# tritiled_v30.net
KiCad netlist of a schematic drawn in EAGLE
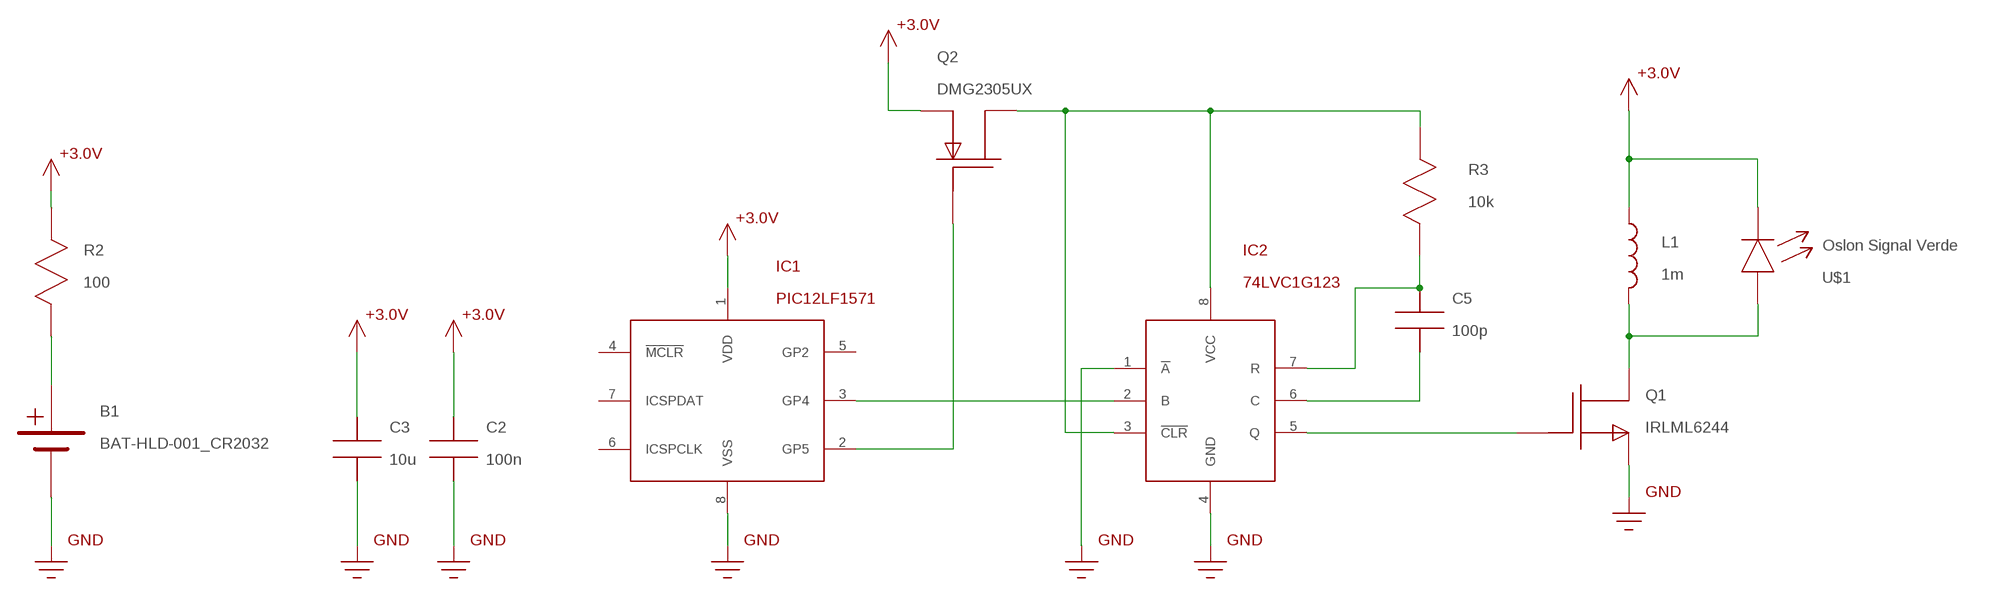
[diagram p0: schematic, sheet 1]

(export (version "E")
  (design (tool "Eeschema 10.0.6"))
  (components
    (comp (ref "B1")
      (value "BAT-HLD-001_CR2032")
      (footprint "eagle-import:CR2032_BAT-HLD_001")
      (libsource (lib "eagle-import") (part "BAT-HLD-001_CR2032"))
    )
    (comp (ref "C2")
      (value "100n")
      (footprint "eagle-import:0805")
      (libsource (lib "eagle-import") (part "C0805"))
    )
    (comp (ref "C3")
      (value "10u")
      (footprint "eagle-import:1206")
      (libsource (lib "eagle-import") (part "C1206"))
    )
    (comp (ref "C5")
      (value "100p")
      (footprint "eagle-import:C0603")
      (libsource (lib "eagle-import") (part "C0603"))
    )
    (comp (ref "IC1")
      (value "PIC12LF1571")
      (footprint "eagle-import:SOIC8")
      (libsource (lib "eagle-import") (part "PIC12LF1571"))
    )
    (comp (ref "IC2")
      (value "74LVC1G123")
      (footprint "eagle-import:SM8")
      (libsource (lib "eagle-import") (part "74LVC1G123"))
    )
    (comp (ref "L1")
      (value "1m")
      (footprint "eagle-import:SRR6028_INDUCTOR")
      (libsource (lib "eagle-import") (part "SRR6028_INDUCTOR"))
    )
    (comp (ref "Q1")
      (value "IRLML6244")
      (footprint "eagle-import:SOT-23")
      (libsource (lib "eagle-import") (part "ZXMN3B01FSOT23"))
    )
    (comp (ref "Q2")
      (value "DMG2305UX")
      (footprint "eagle-import:SOT-23")
      (libsource (lib "eagle-import") (part "DMG2305UXSOT23"))
    )
    (comp (ref "R2")
      (value "100")
      (footprint "eagle-import:R1206")
      (libsource (lib "eagle-import") (part "R1206"))
    )
    (comp (ref "R3")
      (value "10k")
      (footprint "eagle-import:R0603")
      (libsource (lib "eagle-import") (part "R0603"))
    )
    (comp (ref "U$1")
      (value "Oslon Signal Verde")
      (footprint "eagle-import:OSLON_3030_LED")
      (libsource (lib "eagle-import") (part "OSLON_SIGNAL"))
    )
  )
  (nets
    (net (code "1") (name "+3.0V") (class "Default")
      (node (ref "C2") (pin "P$1") (pinfunction "P$1_P$1") (pintype "bidirectional"))
      (node (ref "C3") (pin "P$1") (pinfunction "P$1_P$1") (pintype "bidirectional"))
      (node (ref "IC1") (pin "1") (pinfunction "VDD_1") (pintype "bidirectional"))
      (node (ref "L1") (pin "P$1") (pinfunction "1_P$1") (pintype "passive"))
      (node (ref "Q2") (pin "2") (pinfunction "S_2") (pintype "bidirectional"))
      (node (ref "R2") (pin "P$1") (pinfunction "P$1_P$1") (pintype "bidirectional"))
      (node (ref "U$1") (pin "C") (pinfunction "C_C") (pintype "bidirectional"))
    )
    (net (code "2") (name "GND") (class "Default")
      (node (ref "B1") (pin "GND") (pinfunction "0V_GND") (pintype "power_in"))
      (node (ref "C2") (pin "P$2") (pinfunction "P$2_P$2") (pintype "bidirectional"))
      (node (ref "C3") (pin "P$2") (pinfunction "P$2_P$2") (pintype "bidirectional"))
      (node (ref "IC1") (pin "8") (pinfunction "VSS_8") (pintype "bidirectional"))
      (node (ref "IC2") (pin "1") (pinfunction "~{A}_1") (pintype "bidirectional"))
      (node (ref "IC2") (pin "4") (pinfunction "GND_4") (pintype "bidirectional"))
      (node (ref "Q1") (pin "2") (pinfunction "S_2") (pintype "bidirectional"))
    )
    (net (code "3") (name "Net-(B1-+V-Pad+V1)") (class "Default")
      (node (ref "B1") (pin "+V1") (pinfunction "+V_+V1") (pintype "power_in"))
      (node (ref "B1") (pin "+V2") (pinfunction "+V_+V2") (pintype "power_in"))
      (node (ref "R2") (pin "P$2") (pinfunction "P$2_P$2") (pintype "bidirectional"))
    )
    (net (code "4") (name "Net-(IC1-GP4)") (class "Default")
      (node (ref "IC1") (pin "3") (pinfunction "GP4_3") (pintype "bidirectional"))
      (node (ref "IC2") (pin "2") (pinfunction "B_2") (pintype "bidirectional"))
    )
    (net (code "5") (name "Net-(IC1-GP5)") (class "Default")
      (node (ref "IC1") (pin "2") (pinfunction "GP5_2") (pintype "bidirectional"))
      (node (ref "Q2") (pin "1") (pinfunction "G_1") (pintype "bidirectional"))
    )
    (net (code "6") (name "Net-(IC2-C)") (class "Default")
      (node (ref "C5") (pin "P$2") (pinfunction "P$2_P$2") (pintype "bidirectional"))
      (node (ref "IC2") (pin "6") (pinfunction "C_6") (pintype "bidirectional"))
    )
    (net (code "7") (name "Net-(IC2-Q)") (class "Default")
      (node (ref "IC2") (pin "5") (pinfunction "Q_5") (pintype "bidirectional"))
      (node (ref "Q1") (pin "1") (pinfunction "G_1") (pintype "bidirectional"))
    )
    (net (code "8") (name "Net-(IC2-R)") (class "Default")
      (node (ref "C5") (pin "P$1") (pinfunction "P$1_P$1") (pintype "bidirectional"))
      (node (ref "IC2") (pin "7") (pinfunction "R_7") (pintype "bidirectional"))
      (node (ref "R3") (pin "P$1") (pinfunction "P$1_P$1") (pintype "bidirectional"))
    )
    (net (code "9") (name "Net-(IC2-VCC)") (class "Default")
      (node (ref "IC2") (pin "3") (pinfunction "~{CLR}_3") (pintype "bidirectional"))
      (node (ref "IC2") (pin "8") (pinfunction "VCC_8") (pintype "bidirectional"))
      (node (ref "Q2") (pin "3") (pinfunction "D_3") (pintype "bidirectional"))
      (node (ref "R3") (pin "P$2") (pinfunction "P$2_P$2") (pintype "bidirectional"))
    )
    (net (code "10") (name "Net-(L1-2)") (class "Default")
      (node (ref "L1") (pin "P$2") (pinfunction "2_P$2") (pintype "passive"))
      (node (ref "Q1") (pin "3") (pinfunction "D_3") (pintype "bidirectional"))
      (node (ref "U$1") (pin "A") (pinfunction "A_A") (pintype "bidirectional"))
    )
    (net (code "11") (name "unconnected-(IC1-GP2-Pad5)") (class "Default")
      (node (ref "IC1") (pin "5") (pinfunction "GP2_5") (pintype "bidirectional"))
    )
    (net (code "12") (name "unconnected-(IC1-ICSPCLK-Pad6)") (class "Default")
      (node (ref "IC1") (pin "6") (pinfunction "ICSPCLK_6") (pintype "bidirectional"))
    )
    (net (code "13") (name "unconnected-(IC1-ICSPDAT-Pad7)") (class "Default")
      (node (ref "IC1") (pin "7") (pinfunction "ICSPDAT_7") (pintype "bidirectional"))
    )
    (net (code "14") (name "unconnected-(IC1-~{MCLR}-Pad4)") (class "Default")
      (node (ref "IC1") (pin "4") (pinfunction "~{MCLR}_4") (pintype "bidirectional"))
    )
  )
)
